# switch.net
KiCad netlist of a schematic drawn in Altium Designer
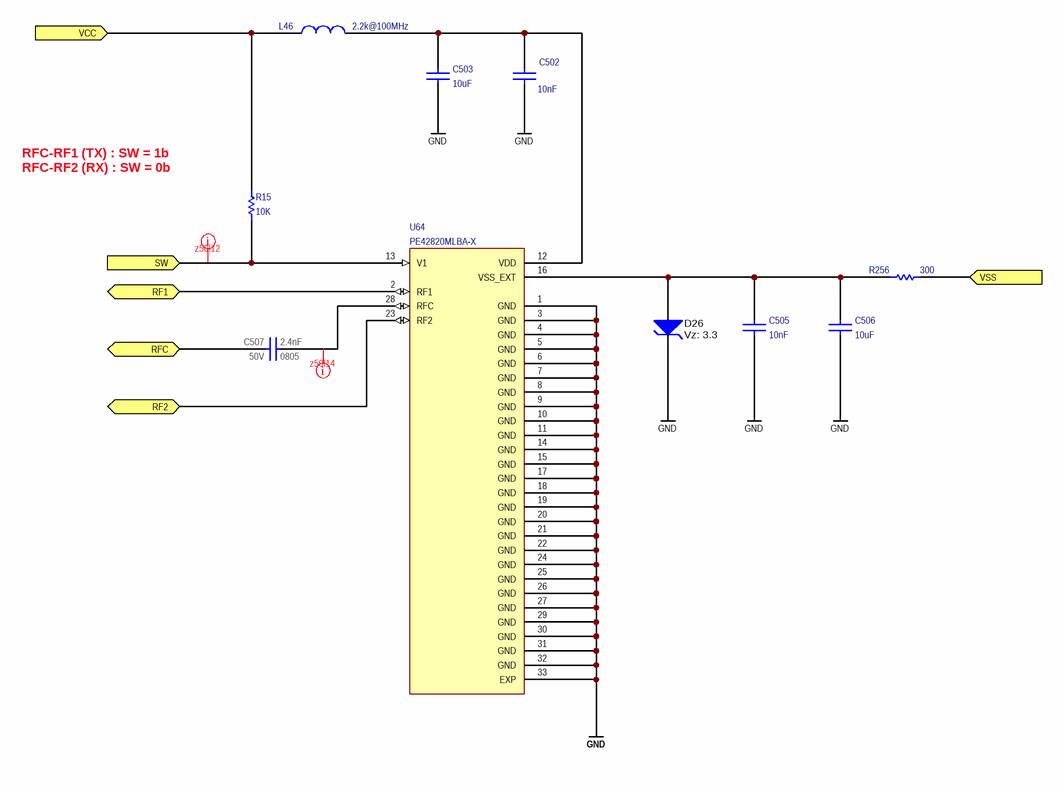
[diagram p0: switch.SchDoc]

(export (version "E")
  (design (tool "Eeschema 10.0.6"))
  (components
    (comp (ref "C502")
      (value "10nF")
      (footprint "CAPC100X50X55L25N")
      (description "Ceramic Capacitor 10nF ±10% 50V X7R 0402")
      (fields (field (name "VOLTAGE") "50V") (field (name "MANUFACTURER") "Murata"))
      (libsource (lib "Graviton") (part "CAP 0402"))
    )
    (comp (ref "C503")
      (value "10uF")
      (footprint "CAPC160X80X90L20N")
      (description "Ceramic Capacitor 10uF ±20% 25V X5R 0603")
      (fields (field (name "MANUFACTURER") "Murata") (field (name "VOLTAGE") "25V"))
      (libsource (lib "generic") (part "CAP 0603"))
    )
    (comp (ref "C505")
      (value "10nF")
      (footprint "CAPC100X50X55L25N")
      (description "Ceramic Capacitor 10nF ±10% 50V X7R 0402")
      (fields (field (name "VOLTAGE") "50V") (field (name "MANUFACTURER") "Murata"))
      (libsource (lib "Graviton") (part "CAP 0402"))
    )
    (comp (ref "C506")
      (value "10uF")
      (footprint "CAPC160X80X90L20N")
      (description "Ceramic Capacitor 10uF ±20% 25V X5R 0603")
      (fields (field (name "MANUFACTURER") "Murata") (field (name "VOLTAGE") "25V"))
      (libsource (lib "generic") (part "CAP 0603"))
    )
    (comp (ref "C507")
      (value "2.4nF")
      (footprint "CAPC2012X145N")
      (description "Ceramic Capacitor 2.4nF 50V 0805")
      (fields
        (field (name "MANUFACTURER") "Dielectric Laboratories")
        (field (name "VOLTAGE") "50V")
        (field (name "PACKAGE") "0805")
        (field (name "Comment") "C08BL242X-5UN-X0T")
      )
      (libsource (lib "generic") (part "CAP"))
    )
    (comp (ref "D26")
      (value "BZT585B3V3T-7")
      (footprint "generic:SOD523")
      (description "3.3V Zener Diode SOD-523")
      (fields (field (name "MANUFACTURER") "Diodes Inc") (field (name "VZ") "3.3"))
      (libsource (lib "generic") (part "ZENER"))
    )
    (comp (ref "L46")
      (value "2.2k@100MHz")
      (footprint "INDC1005X55N")
      (description "Ferrite Bead 2.2k@100MHz 150mA 0402")
      (fields (field (name "MANUFACTURER") "TDK") (field (name "Comment") "MMZ1005A222ET000"))
      (libsource (lib "*") (part "INDUCTANCE1"))
    )
    (comp (ref "R15")
      (value "10K")
      (footprint "RESC1005X40N")
      (description "Thick Film Resistor 10k ±1% 0.1W 50V 0402")
      (fields (field (name "MANUFACTURER") "Panasonic") (field (name "TOLERANCE") "±1%"))
      (libsource (lib "Graviton") (part "RES 0402"))
    )
    (comp (ref "R256")
      (value "300")
      (footprint "RESC2012X70N")
      (description "Thin Film Resistor 300 +/-0.1% SMD 0805")
      (fields (field (name "TOLERANCE") "±0.1%") (field (name "MANUFACTURER") "Susumu"))
      (libsource (lib "generic") (part "RES"))
    )
    (comp (ref "U64")
      (value "PE42820MLBA-X")
      (footprint "QFN50P500X500X90-32N")
      (description "RF Switch SPDT 30MHz to 2.7GHz 23dB 32-Pin QFN EP T/R")
      (fields (field (name "MANUFACTURER") "Peregrine Semiconductor"))
      (libsource (lib "peregrine") (part "PE42820MLBA-X"))
    )
  )
  (nets
    (net (code "1") (name "/RF1") (class "Default")
      (node (ref "U64") (pin "2") (pinfunction "RF1_2") (pintype "bidirectional"))
    )
    (net (code "2") (name "/RF2") (class "Default")
      (node (ref "U64") (pin "23") (pinfunction "RF2_23") (pintype "bidirectional"))
    )
    (net (code "3") (name "/RFC") (class "Default")
      (node (ref "C507") (pin "2") (pinfunction "2_2") (pintype "passive"))
    )
    (net (code "4") (name "/SW") (class "Default")
      (node (ref "R15") (pin "1") (pinfunction "1_1") (pintype "passive"))
      (node (ref "U64") (pin "13") (pinfunction "V1_13") (pintype "input"))
    )
    (net (code "5") (name "/VCC") (class "Default")
      (node (ref "L46") (pin "1") (pinfunction "1_1") (pintype "passive"))
      (node (ref "R15") (pin "2") (pinfunction "2_2") (pintype "passive"))
    )
    (net (code "6") (name "/VSS") (class "Default")
      (node (ref "R256") (pin "2") (pinfunction "2_2") (pintype "passive"))
    )
    (net (code "7") (name "GND") (class "Default")
      (node (ref "C502") (pin "1") (pinfunction "1_1") (pintype "passive"))
      (node (ref "C503") (pin "1") (pinfunction "1_1") (pintype "passive"))
      (node (ref "C505") (pin "1") (pinfunction "1_1") (pintype "passive"))
      (node (ref "C506") (pin "1") (pinfunction "1_1") (pintype "passive"))
      (node (ref "D26") (pin "1") (pinfunction "K_1") (pintype "passive"))
      (node (ref "U64") (pin "1") (pinfunction "GND_1") (pintype "power_in"))
      (node (ref "U64") (pin "10") (pinfunction "GND_10") (pintype "power_in"))
      (node (ref "U64") (pin "11") (pinfunction "GND_11") (pintype "power_in"))
      (node (ref "U64") (pin "14") (pinfunction "GND_14") (pintype "power_in"))
      (node (ref "U64") (pin "15") (pinfunction "GND_15") (pintype "power_in"))
      (node (ref "U64") (pin "17") (pinfunction "GND_17") (pintype "power_in"))
      (node (ref "U64") (pin "18") (pinfunction "GND_18") (pintype "power_in"))
      (node (ref "U64") (pin "19") (pinfunction "GND_19") (pintype "power_in"))
      (node (ref "U64") (pin "20") (pinfunction "GND_20") (pintype "power_in"))
      (node (ref "U64") (pin "21") (pinfunction "GND_21") (pintype "power_in"))
      (node (ref "U64") (pin "22") (pinfunction "GND_22") (pintype "power_in"))
      (node (ref "U64") (pin "24") (pinfunction "GND_24") (pintype "power_in"))
      (node (ref "U64") (pin "25") (pinfunction "GND_25") (pintype "power_in"))
      (node (ref "U64") (pin "26") (pinfunction "GND_26") (pintype "power_in"))
      (node (ref "U64") (pin "27") (pinfunction "GND_27") (pintype "power_in"))
      (node (ref "U64") (pin "29") (pinfunction "GND_29") (pintype "power_in"))
      (node (ref "U64") (pin "3") (pinfunction "GND_3") (pintype "power_in"))
      (node (ref "U64") (pin "30") (pinfunction "GND_30") (pintype "power_in"))
      (node (ref "U64") (pin "31") (pinfunction "GND_31") (pintype "power_in"))
      (node (ref "U64") (pin "32") (pinfunction "GND_32") (pintype "power_in"))
      (node (ref "U64") (pin "33") (pinfunction "EXP_33") (pintype "power_in"))
      (node (ref "U64") (pin "4") (pinfunction "GND_4") (pintype "power_in"))
      (node (ref "U64") (pin "5") (pinfunction "GND_5") (pintype "power_in"))
      (node (ref "U64") (pin "6") (pinfunction "GND_6") (pintype "power_in"))
      (node (ref "U64") (pin "7") (pinfunction "GND_7") (pintype "power_in"))
      (node (ref "U64") (pin "8") (pinfunction "GND_8") (pintype "power_in"))
      (node (ref "U64") (pin "9") (pinfunction "GND_9") (pintype "power_in"))
    )
    (net (code "8") (name "Net-(D26-A)") (class "Default")
      (node (ref "C505") (pin "2") (pinfunction "2_2") (pintype "passive"))
      (node (ref "C506") (pin "2") (pinfunction "2_2") (pintype "passive"))
      (node (ref "D26") (pin "2") (pinfunction "A_2") (pintype "power_in"))
      (node (ref "R256") (pin "1") (pinfunction "1_1") (pintype "passive"))
      (node (ref "U64") (pin "16") (pinfunction "VSS_EXT_16") (pintype "power_in"))
    )
    (net (code "9") (name "Net-(U64-RFC)") (class "Default")
      (node (ref "C507") (pin "1") (pinfunction "1_1") (pintype "passive"))
      (node (ref "U64") (pin "28") (pinfunction "RFC_28") (pintype "bidirectional"))
    )
    (net (code "10") (name "Net-(U64-VDD)") (class "Default")
      (node (ref "C502") (pin "2") (pinfunction "2_2") (pintype "passive"))
      (node (ref "C503") (pin "2") (pinfunction "2_2") (pintype "passive"))
      (node (ref "L46") (pin "2") (pinfunction "2_2") (pintype "passive"))
      (node (ref "U64") (pin "12") (pinfunction "VDD_12") (pintype "power_in"))
    )
  )
)
